# M502X.net
KiCad netlist of a schematic drawn in EAGLE
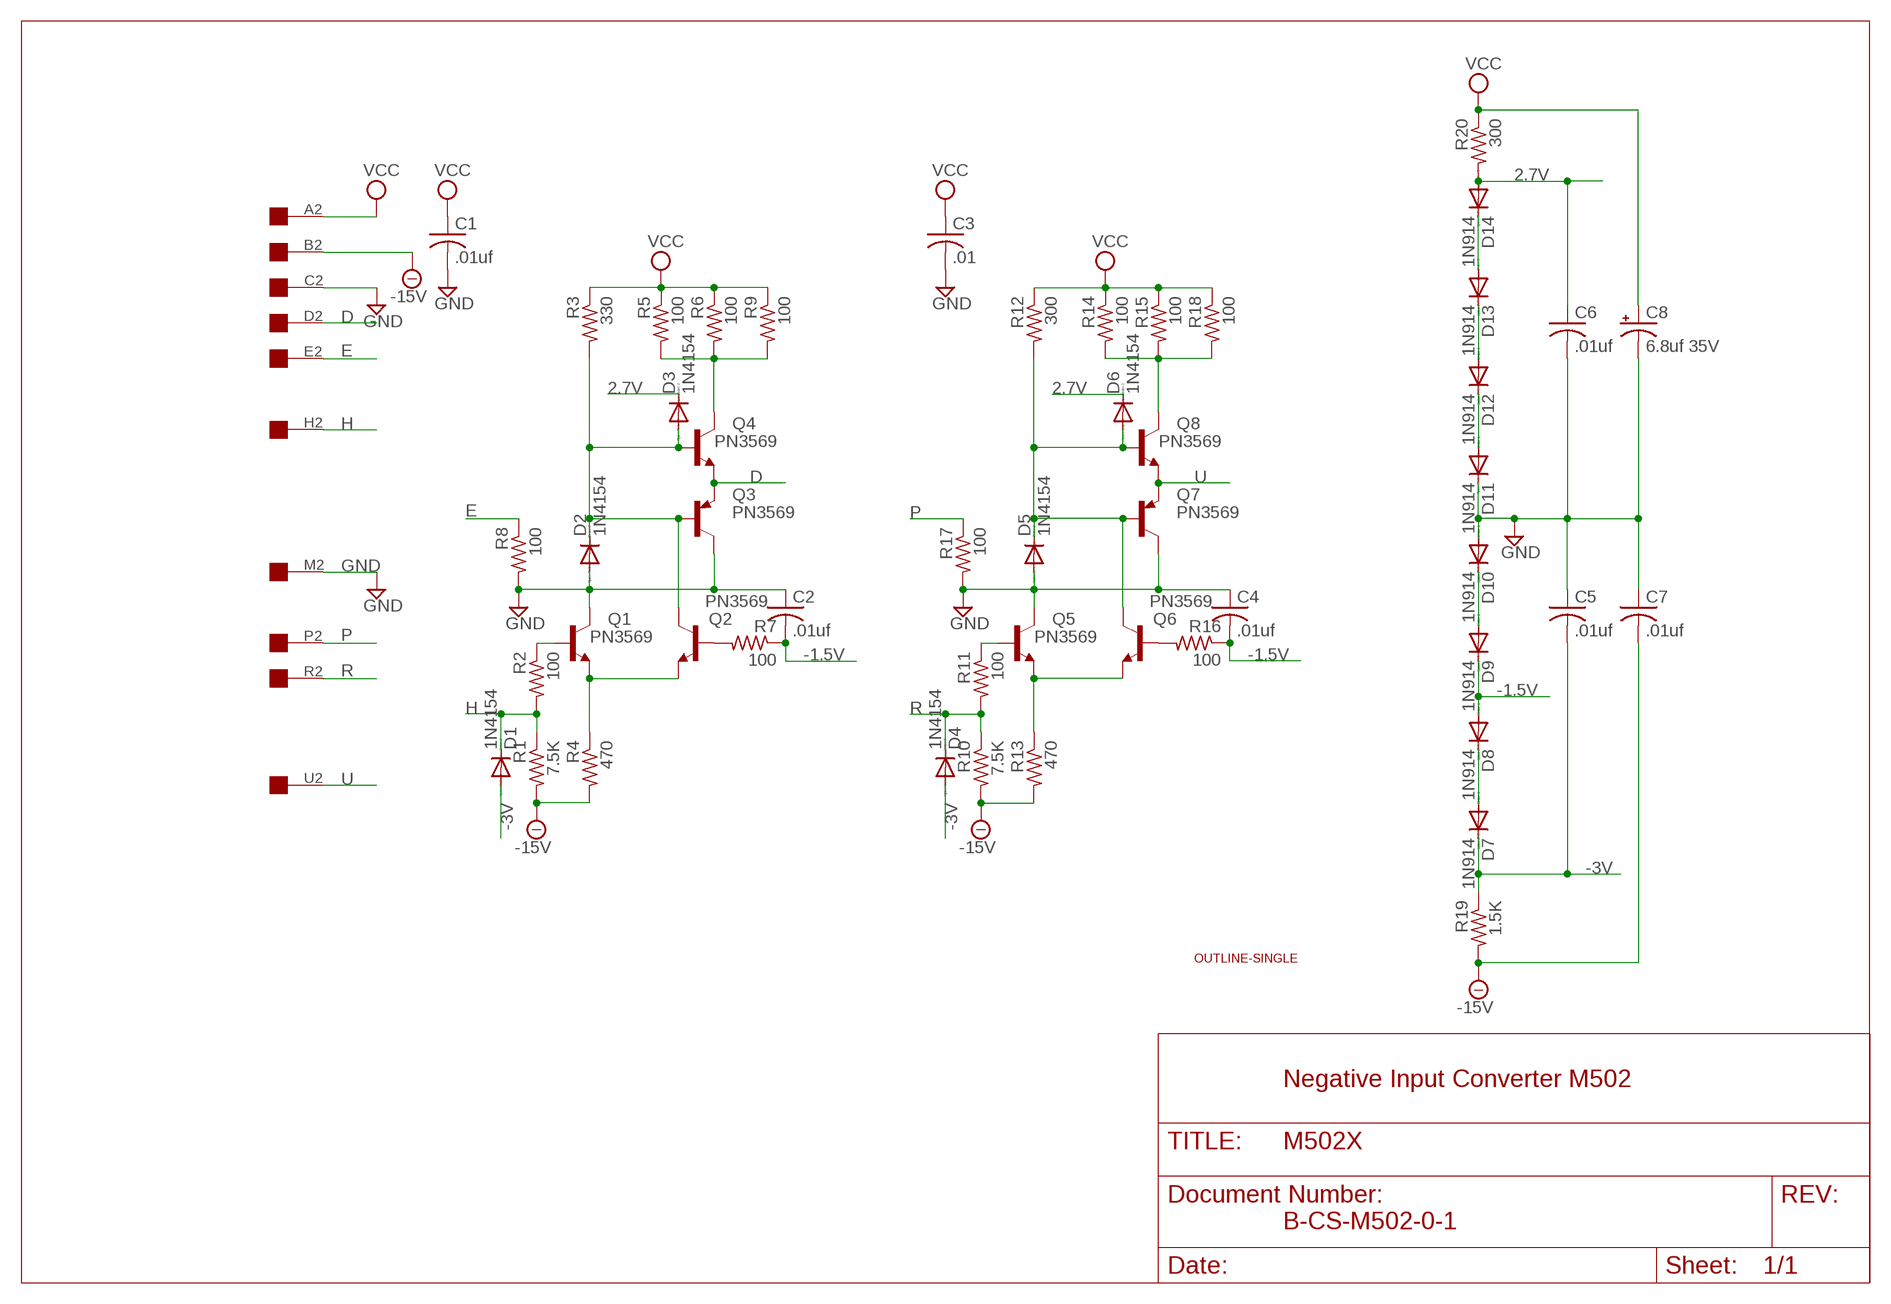
[diagram p0: schematic, sheet 1]

(export (version "E")
  (design (tool "Eeschema 10.0.6"))
  (components
    (comp (ref "C1")
      (value ".01uf")
      (footprint "eagle-import:C050-025X075")
      (libsource (lib "eagle-import") (part "C-US050-025X075"))
    )
    (comp (ref "C2")
      (value ".01uf")
      (footprint "eagle-import:C050-025X075")
      (libsource (lib "eagle-import") (part "C-US050-025X075"))
    )
    (comp (ref "C3")
      (value ".01")
      (footprint "eagle-import:C050-025X075")
      (libsource (lib "eagle-import") (part "C-US050-025X075"))
    )
    (comp (ref "C4")
      (value ".01uf")
      (footprint "eagle-import:C050-025X075")
      (libsource (lib "eagle-import") (part "C-US050-025X075"))
    )
    (comp (ref "C5")
      (value ".01uf")
      (footprint "eagle-import:C050-025X075")
      (libsource (lib "eagle-import") (part "C-US050-025X075"))
    )
    (comp (ref "C6")
      (value ".01uf")
      (footprint "eagle-import:C050-025X075")
      (libsource (lib "eagle-import") (part "C-US050-025X075"))
    )
    (comp (ref "C7")
      (value ".01uf")
      (footprint "eagle-import:C050-025X075")
      (libsource (lib "eagle-import") (part "C-US050-025X075"))
    )
    (comp (ref "C8")
      (value "6.8uf 35V")
      (footprint "eagle-import:E15-5")
      (libsource (lib "eagle-import") (part "CPOL-USE15-5AXIAL"))
    )
    (comp (ref "D1")
      (value "1N4154")
      (footprint "eagle-import:DO41-10")
      (libsource (lib "eagle-import") (part "1N4004"))
    )
    (comp (ref "D2")
      (value "1N4154")
      (footprint "eagle-import:DO41-10")
      (libsource (lib "eagle-import") (part "1N4004"))
    )
    (comp (ref "D3")
      (value "1N4154")
      (footprint "eagle-import:DO41-10")
      (libsource (lib "eagle-import") (part "1N4004"))
    )
    (comp (ref "D4")
      (value "1N4154")
      (footprint "eagle-import:DO41-10")
      (libsource (lib "eagle-import") (part "1N4004"))
    )
    (comp (ref "D5")
      (value "1N4154")
      (footprint "eagle-import:DO41-10")
      (libsource (lib "eagle-import") (part "1N4004"))
    )
    (comp (ref "D6")
      (value "1N4154")
      (footprint "eagle-import:DO41-10")
      (libsource (lib "eagle-import") (part "1N4004"))
    )
    (comp (ref "D7")
      (value "1N914")
      (footprint "eagle-import:DO41-10")
      (libsource (lib "eagle-import") (part "1N4004"))
    )
    (comp (ref "D8")
      (value "1N914")
      (footprint "eagle-import:DO41-10")
      (libsource (lib "eagle-import") (part "1N4004"))
    )
    (comp (ref "D9")
      (value "1N914")
      (footprint "eagle-import:DO41-10")
      (libsource (lib "eagle-import") (part "1N4004"))
    )
    (comp (ref "D10")
      (value "1N914")
      (footprint "eagle-import:DO41-10")
      (libsource (lib "eagle-import") (part "1N4004"))
    )
    (comp (ref "D11")
      (value "1N914")
      (footprint "eagle-import:DO41-10")
      (libsource (lib "eagle-import") (part "1N4004"))
    )
    (comp (ref "D12")
      (value "1N914")
      (footprint "eagle-import:DO41-10")
      (libsource (lib "eagle-import") (part "1N4004"))
    )
    (comp (ref "D13")
      (value "1N914")
      (footprint "eagle-import:DO41-10")
      (libsource (lib "eagle-import") (part "1N4004"))
    )
    (comp (ref "D14")
      (value "1N914")
      (footprint "eagle-import:DO41-10")
      (libsource (lib "eagle-import") (part "1N4004"))
    )
    (comp (ref "Q1")
      (value "PN3569")
      (footprint "eagle-import:TO39")
      (libsource (lib "eagle-import") (part "2N1711"))
    )
    (comp (ref "Q2")
      (value "PN3569")
      (footprint "eagle-import:TO39")
      (libsource (lib "eagle-import") (part "2N1711"))
    )
    (comp (ref "Q3")
      (value "PN3569")
      (footprint "eagle-import:TO39")
      (libsource (lib "eagle-import") (part "2N5415"))
    )
    (comp (ref "Q4")
      (value "PN3569")
      (footprint "eagle-import:TO39")
      (libsource (lib "eagle-import") (part "2N1711"))
    )
    (comp (ref "Q5")
      (value "PN3569")
      (footprint "eagle-import:TO39")
      (libsource (lib "eagle-import") (part "2N1711"))
    )
    (comp (ref "Q6")
      (value "PN3569")
      (footprint "eagle-import:TO39")
      (libsource (lib "eagle-import") (part "2N1711"))
    )
    (comp (ref "Q7")
      (value "PN3569")
      (footprint "eagle-import:TO39")
      (libsource (lib "eagle-import") (part "2N5415"))
    )
    (comp (ref "Q8")
      (value "PN3569")
      (footprint "eagle-import:TO39")
      (libsource (lib "eagle-import") (part "2N1711"))
    )
    (comp (ref "R1")
      (value "7.5K")
      (footprint "eagle-import:0207_10")
      (libsource (lib "eagle-import") (part "R-US_0207/10"))
    )
    (comp (ref "R2")
      (value "100")
      (footprint "eagle-import:0207_10")
      (libsource (lib "eagle-import") (part "R-US_0207/10"))
    )
    (comp (ref "R3")
      (value "330")
      (footprint "eagle-import:0207_10")
      (libsource (lib "eagle-import") (part "R-US_0207/10"))
    )
    (comp (ref "R4")
      (value "470")
      (footprint "eagle-import:0207_10")
      (libsource (lib "eagle-import") (part "R-US_0207/10"))
    )
    (comp (ref "R5")
      (value "100")
      (footprint "eagle-import:0207_10")
      (libsource (lib "eagle-import") (part "R-US_0207/10"))
    )
    (comp (ref "R6")
      (value "100")
      (footprint "eagle-import:0207_10")
      (libsource (lib "eagle-import") (part "R-US_0207/10"))
    )
    (comp (ref "R7")
      (value "100")
      (footprint "eagle-import:0207_10")
      (libsource (lib "eagle-import") (part "R-US_0207/10"))
    )
    (comp (ref "R8")
      (value "100")
      (footprint "eagle-import:0207_10")
      (libsource (lib "eagle-import") (part "R-US_0207/10"))
    )
    (comp (ref "R9")
      (value "100")
      (footprint "eagle-import:0207_10")
      (libsource (lib "eagle-import") (part "R-US_0207/10"))
    )
    (comp (ref "R10")
      (value "7.5K")
      (footprint "eagle-import:0207_10")
      (libsource (lib "eagle-import") (part "R-US_0207/10"))
    )
    (comp (ref "R11")
      (value "100")
      (footprint "eagle-import:0207_10")
      (libsource (lib "eagle-import") (part "R-US_0207/10"))
    )
    (comp (ref "R12")
      (value "300")
      (footprint "eagle-import:0207_10")
      (libsource (lib "eagle-import") (part "R-US_0207/10"))
    )
    (comp (ref "R13")
      (value "470")
      (footprint "eagle-import:0207_10")
      (libsource (lib "eagle-import") (part "R-US_0207/10"))
    )
    (comp (ref "R14")
      (value "100")
      (footprint "eagle-import:0207_10")
      (libsource (lib "eagle-import") (part "R-US_0207/10"))
    )
    (comp (ref "R15")
      (value "100")
      (footprint "eagle-import:0207_10")
      (libsource (lib "eagle-import") (part "R-US_0207/10"))
    )
    (comp (ref "R16")
      (value "100")
      (footprint "eagle-import:0207_10")
      (libsource (lib "eagle-import") (part "R-US_0207/10"))
    )
    (comp (ref "R17")
      (value "100")
      (footprint "eagle-import:0207_10")
      (libsource (lib "eagle-import") (part "R-US_0207/10"))
    )
    (comp (ref "R18")
      (value "100")
      (footprint "eagle-import:0207_10")
      (libsource (lib "eagle-import") (part "R-US_0207/10"))
    )
    (comp (ref "R19")
      (value "1.5K")
      (footprint "eagle-import:0207_10")
      (libsource (lib "eagle-import") (part "R-US_0207/10"))
    )
    (comp (ref "R20")
      (value "300")
      (footprint "eagle-import:0207_10")
      (libsource (lib "eagle-import") (part "R-US_0207/10"))
    )
    (comp (ref "U$1")
      (value "EDGE-1")
      (footprint "eagle-import:EDGE-CON1")
      (libsource (lib "eagle-import") (part "EDGE-1"))
    )
    (comp (ref "U$2")
      (value "OUTLINE-SINGLE")
      (footprint "eagle-import:SINGLE")
      (libsource (lib "eagle-import") (part "OUTLINE-SINGLE"))
    )
  )
  (nets
    (net (code "1") (name "-15V") (class "Default")
      (node (ref "C7") (pin "2") (pinfunction "2_2") (pintype "passive"))
      (node (ref "R1") (pin "2") (pinfunction "2_2") (pintype "passive"))
      (node (ref "R10") (pin "2") (pinfunction "2_2") (pintype "passive"))
      (node (ref "R13") (pin "2") (pinfunction "2_2") (pintype "passive"))
      (node (ref "R19") (pin "2") (pinfunction "2_2") (pintype "passive"))
      (node (ref "R4") (pin "2") (pinfunction "2_2") (pintype "passive"))
      (node (ref "U$1") (pin "B2") (pinfunction "1_B2") (pintype "bidirectional"))
    )
    (net (code "2") (name "/-1.5V") (class "Default")
      (node (ref "C2") (pin "2") (pinfunction "2_2") (pintype "passive"))
      (node (ref "C4") (pin "2") (pinfunction "2_2") (pintype "passive"))
      (node (ref "D8") (pin "A") (pinfunction "A_A") (pintype "passive"))
      (node (ref "D9") (pin "C") (pinfunction "C_C") (pintype "passive"))
      (node (ref "R16") (pin "1") (pinfunction "1_1") (pintype "passive"))
      (node (ref "R7") (pin "1") (pinfunction "1_1") (pintype "passive"))
    )
    (net (code "3") (name "/-3V") (class "Default")
      (node (ref "C5") (pin "2") (pinfunction "2_2") (pintype "passive"))
      (node (ref "D1") (pin "A") (pinfunction "A_A") (pintype "passive"))
      (node (ref "D4") (pin "A") (pinfunction "A_A") (pintype "passive"))
      (node (ref "D7") (pin "C") (pinfunction "C_C") (pintype "passive"))
      (node (ref "R19") (pin "1") (pinfunction "1_1") (pintype "passive"))
    )
    (net (code "4") (name "/2.7V") (class "Default")
      (node (ref "C6") (pin "1") (pinfunction "1_1") (pintype "passive"))
      (node (ref "D14") (pin "A") (pinfunction "A_A") (pintype "passive"))
      (node (ref "D3") (pin "C") (pinfunction "C_C") (pintype "passive"))
      (node (ref "D6") (pin "C") (pinfunction "C_C") (pintype "passive"))
      (node (ref "R20") (pin "2") (pinfunction "2_2") (pintype "passive"))
    )
    (net (code "5") (name "/D") (class "Default")
      (node (ref "Q3") (pin "1") (pinfunction "E_1") (pintype "passive"))
      (node (ref "Q4") (pin "1") (pinfunction "E_1") (pintype "passive"))
      (node (ref "U$1") (pin "D2") (pinfunction "1_D2") (pintype "bidirectional"))
    )
    (net (code "6") (name "/E") (class "Default")
      (node (ref "R8") (pin "1") (pinfunction "1_1") (pintype "passive"))
      (node (ref "U$1") (pin "E2") (pinfunction "1_E2") (pintype "bidirectional"))
    )
    (net (code "7") (name "/H") (class "Default")
      (node (ref "D1") (pin "C") (pinfunction "C_C") (pintype "passive"))
      (node (ref "R1") (pin "1") (pinfunction "1_1") (pintype "passive"))
      (node (ref "R2") (pin "2") (pinfunction "2_2") (pintype "passive"))
      (node (ref "U$1") (pin "H2") (pinfunction "1_H2") (pintype "bidirectional"))
    )
    (net (code "8") (name "/P") (class "Default")
      (node (ref "R17") (pin "1") (pinfunction "1_1") (pintype "passive"))
      (node (ref "U$1") (pin "P2") (pinfunction "1_P2") (pintype "bidirectional"))
    )
    (net (code "9") (name "/R") (class "Default")
      (node (ref "D4") (pin "C") (pinfunction "C_C") (pintype "passive"))
      (node (ref "R10") (pin "1") (pinfunction "1_1") (pintype "passive"))
      (node (ref "R11") (pin "2") (pinfunction "2_2") (pintype "passive"))
      (node (ref "U$1") (pin "R2") (pinfunction "1_R2") (pintype "bidirectional"))
    )
    (net (code "10") (name "/U") (class "Default")
      (node (ref "Q7") (pin "1") (pinfunction "E_1") (pintype "passive"))
      (node (ref "Q8") (pin "1") (pinfunction "E_1") (pintype "passive"))
      (node (ref "U$1") (pin "U2") (pinfunction "1_U2") (pintype "bidirectional"))
    )
    (net (code "11") (name "GND") (class "Default")
      (node (ref "C1") (pin "2") (pinfunction "2_2") (pintype "passive"))
      (node (ref "C2") (pin "1") (pinfunction "1_1") (pintype "passive"))
      (node (ref "C3") (pin "2") (pinfunction "2_2") (pintype "passive"))
      (node (ref "C4") (pin "1") (pinfunction "1_1") (pintype "passive"))
      (node (ref "C5") (pin "1") (pinfunction "1_1") (pintype "passive"))
      (node (ref "C6") (pin "2") (pinfunction "2_2") (pintype "passive"))
      (node (ref "C7") (pin "1") (pinfunction "1_1") (pintype "passive"))
      (node (ref "C8") (pin "-") (pinfunction "-_-") (pintype "passive"))
      (node (ref "D10") (pin "A") (pinfunction "A_A") (pintype "passive"))
      (node (ref "D11") (pin "C") (pinfunction "C_C") (pintype "passive"))
      (node (ref "D2") (pin "A") (pinfunction "A_A") (pintype "passive"))
      (node (ref "D5") (pin "A") (pinfunction "A_A") (pintype "passive"))
      (node (ref "Q1") (pin "3") (pinfunction "C_3") (pintype "passive"))
      (node (ref "Q3") (pin "3") (pinfunction "C_3") (pintype "passive"))
      (node (ref "Q5") (pin "3") (pinfunction "C_3") (pintype "passive"))
      (node (ref "Q7") (pin "3") (pinfunction "C_3") (pintype "passive"))
      (node (ref "R17") (pin "2") (pinfunction "2_2") (pintype "passive"))
      (node (ref "R8") (pin "2") (pinfunction "2_2") (pintype "passive"))
      (node (ref "U$1") (pin "C2") (pinfunction "1_C2") (pintype "bidirectional"))
      (node (ref "U$1") (pin "M2") (pinfunction "1_M2") (pintype "bidirectional"))
    )
    (net (code "12") (name "Net-(D7-PadA)") (class "Default")
      (node (ref "D7") (pin "A") (pinfunction "A_A") (pintype "passive"))
      (node (ref "D8") (pin "C") (pinfunction "C_C") (pintype "passive"))
    )
    (net (code "13") (name "Net-(D10-PadC)") (class "Default")
      (node (ref "D10") (pin "C") (pinfunction "C_C") (pintype "passive"))
      (node (ref "D9") (pin "A") (pinfunction "A_A") (pintype "passive"))
    )
    (net (code "14") (name "Net-(D11-PadA)") (class "Default")
      (node (ref "D11") (pin "A") (pinfunction "A_A") (pintype "passive"))
      (node (ref "D12") (pin "C") (pinfunction "C_C") (pintype "passive"))
    )
    (net (code "15") (name "Net-(D12-PadA)") (class "Default")
      (node (ref "D12") (pin "A") (pinfunction "A_A") (pintype "passive"))
      (node (ref "D13") (pin "C") (pinfunction "C_C") (pintype "passive"))
    )
    (net (code "16") (name "Net-(D13-PadA)") (class "Default")
      (node (ref "D13") (pin "A") (pinfunction "A_A") (pintype "passive"))
      (node (ref "D14") (pin "C") (pinfunction "C_C") (pintype "passive"))
    )
    (net (code "17") (name "Net-(Q1-B)") (class "Default")
      (node (ref "Q1") (pin "2") (pinfunction "B_2") (pintype "passive"))
      (node (ref "R2") (pin "1") (pinfunction "1_1") (pintype "passive"))
    )
    (net (code "18") (name "Net-(Q1-E)") (class "Default")
      (node (ref "Q1") (pin "1") (pinfunction "E_1") (pintype "passive"))
      (node (ref "Q2") (pin "1") (pinfunction "E_1") (pintype "passive"))
      (node (ref "R4") (pin "1") (pinfunction "1_1") (pintype "passive"))
    )
    (net (code "19") (name "Net-(Q2-B)") (class "Default")
      (node (ref "Q2") (pin "2") (pinfunction "B_2") (pintype "passive"))
      (node (ref "R7") (pin "2") (pinfunction "2_2") (pintype "passive"))
    )
    (net (code "20") (name "Net-(Q2-C)") (class "Default")
      (node (ref "D2") (pin "C") (pinfunction "C_C") (pintype "passive"))
      (node (ref "D3") (pin "A") (pinfunction "A_A") (pintype "passive"))
      (node (ref "Q2") (pin "3") (pinfunction "C_3") (pintype "passive"))
      (node (ref "Q3") (pin "2") (pinfunction "B_2") (pintype "passive"))
      (node (ref "Q4") (pin "2") (pinfunction "B_2") (pintype "passive"))
      (node (ref "R3") (pin "2") (pinfunction "2_2") (pintype "passive"))
    )
    (net (code "21") (name "Net-(Q4-C)") (class "Default")
      (node (ref "Q4") (pin "3") (pinfunction "C_3") (pintype "passive"))
      (node (ref "R5") (pin "2") (pinfunction "2_2") (pintype "passive"))
      (node (ref "R6") (pin "2") (pinfunction "2_2") (pintype "passive"))
      (node (ref "R9") (pin "2") (pinfunction "2_2") (pintype "passive"))
    )
    (net (code "22") (name "Net-(Q5-B)") (class "Default")
      (node (ref "Q5") (pin "2") (pinfunction "B_2") (pintype "passive"))
      (node (ref "R11") (pin "1") (pinfunction "1_1") (pintype "passive"))
    )
    (net (code "23") (name "Net-(Q5-E)") (class "Default")
      (node (ref "Q5") (pin "1") (pinfunction "E_1") (pintype "passive"))
      (node (ref "Q6") (pin "1") (pinfunction "E_1") (pintype "passive"))
      (node (ref "R13") (pin "1") (pinfunction "1_1") (pintype "passive"))
    )
    (net (code "24") (name "Net-(Q6-B)") (class "Default")
      (node (ref "Q6") (pin "2") (pinfunction "B_2") (pintype "passive"))
      (node (ref "R16") (pin "2") (pinfunction "2_2") (pintype "passive"))
    )
    (net (code "25") (name "Net-(Q6-C)") (class "Default")
      (node (ref "D5") (pin "C") (pinfunction "C_C") (pintype "passive"))
      (node (ref "D6") (pin "A") (pinfunction "A_A") (pintype "passive"))
      (node (ref "Q6") (pin "3") (pinfunction "C_3") (pintype "passive"))
      (node (ref "Q7") (pin "2") (pinfunction "B_2") (pintype "passive"))
      (node (ref "Q8") (pin "2") (pinfunction "B_2") (pintype "passive"))
      (node (ref "R12") (pin "2") (pinfunction "2_2") (pintype "passive"))
    )
    (net (code "26") (name "Net-(Q8-C)") (class "Default")
      (node (ref "Q8") (pin "3") (pinfunction "C_3") (pintype "passive"))
      (node (ref "R14") (pin "2") (pinfunction "2_2") (pintype "passive"))
      (node (ref "R15") (pin "2") (pinfunction "2_2") (pintype "passive"))
      (node (ref "R18") (pin "2") (pinfunction "2_2") (pintype "passive"))
    )
    (net (code "27") (name "VCC") (class "Default")
      (node (ref "C1") (pin "1") (pinfunction "1_1") (pintype "passive"))
      (node (ref "C3") (pin "1") (pinfunction "1_1") (pintype "passive"))
      (node (ref "C8") (pin "+") (pinfunction "+_+") (pintype "passive"))
      (node (ref "R12") (pin "1") (pinfunction "1_1") (pintype "passive"))
      (node (ref "R14") (pin "1") (pinfunction "1_1") (pintype "passive"))
      (node (ref "R15") (pin "1") (pinfunction "1_1") (pintype "passive"))
      (node (ref "R18") (pin "1") (pinfunction "1_1") (pintype "passive"))
      (node (ref "R20") (pin "1") (pinfunction "1_1") (pintype "passive"))
      (node (ref "R3") (pin "1") (pinfunction "1_1") (pintype "passive"))
      (node (ref "R5") (pin "1") (pinfunction "1_1") (pintype "passive"))
      (node (ref "R6") (pin "1") (pinfunction "1_1") (pintype "passive"))
      (node (ref "R9") (pin "1") (pinfunction "1_1") (pintype "passive"))
      (node (ref "U$1") (pin "A2") (pinfunction "1_A2") (pintype "bidirectional"))
    )
  )
)
